# Dual_VCO_schematic_Thijn_en_Ralph.net
KiCad netlist of a schematic drawn in Altium Designer
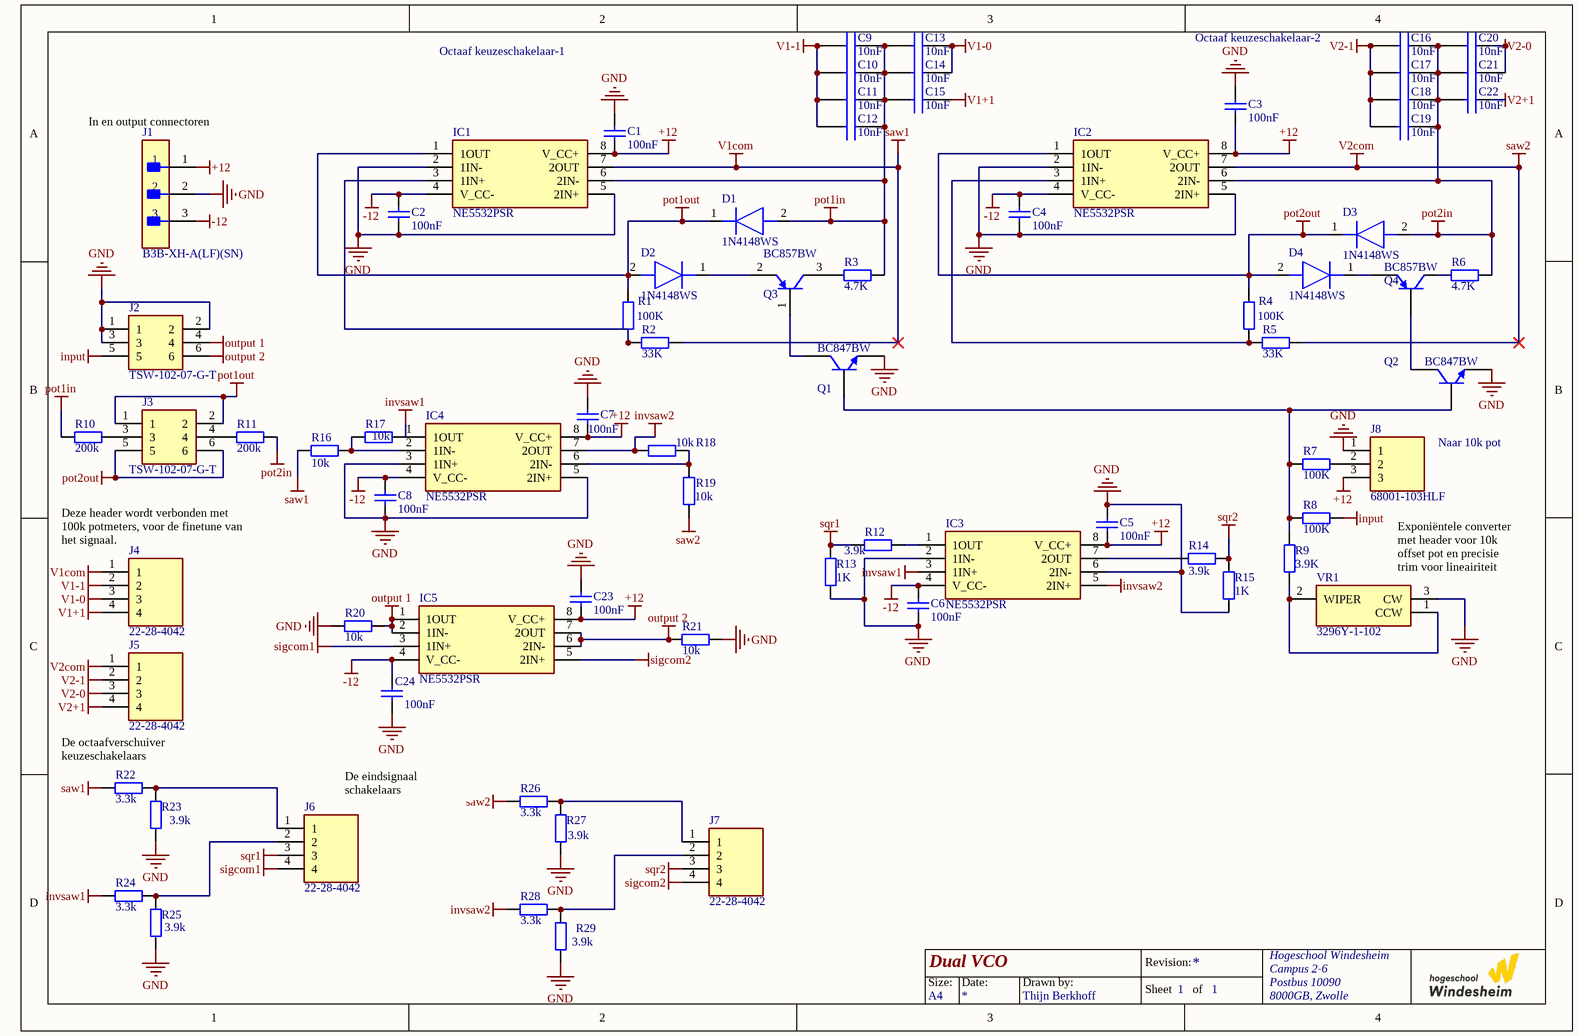
[diagram p0: Dual VCO schematic Thijn en Ralph.SchDoc]

(export (version "E")
  (design (tool "Eeschema 10.0.6"))
  (components
    (comp (ref "C1")
      (value "100nF")
      (footprint "C1206")
      (description "SMD Capacitor 1206")
      (fields (field (name "PUBLISHER") "Windesheim"))
      (libsource (lib "KookwekkerLibrary_v5_1") (part "Capacitor_1206"))
    )
    (comp (ref "C2")
      (value "100nF")
      (footprint "C1206")
      (description "SMD Capacitor 1206")
      (fields (field (name "PUBLISHER") "Windesheim"))
      (libsource (lib "KookwekkerLibrary_v5_1") (part "Capacitor_1206"))
    )
    (comp (ref "C3")
      (value "100nF")
      (footprint "C1206")
      (description "SMD Capacitor 1206")
      (fields (field (name "PUBLISHER") "Windesheim"))
      (libsource (lib "KookwekkerLibrary_v5_1") (part "Capacitor_1206"))
    )
    (comp (ref "C4")
      (value "100nF")
      (footprint "C1206")
      (description "SMD Capacitor 1206")
      (fields (field (name "PUBLISHER") "Windesheim"))
      (libsource (lib "KookwekkerLibrary_v5_1") (part "Capacitor_1206"))
    )
    (comp (ref "C5")
      (value "100nF")
      (footprint "C1206")
      (description "SMD Capacitor 1206")
      (fields (field (name "PUBLISHER") "Windesheim"))
      (libsource (lib "KookwekkerLibrary_v5_1") (part "Capacitor_1206"))
    )
    (comp (ref "C6")
      (value "100nF")
      (footprint "C1206")
      (description "SMD Capacitor 1206")
      (fields (field (name "PUBLISHER") "Windesheim"))
      (libsource (lib "KookwekkerLibrary_v5_1") (part "Capacitor_1206"))
    )
    (comp (ref "C7")
      (value "100nF")
      (footprint "C1206")
      (description "SMD Capacitor 1206")
      (fields (field (name "PUBLISHER") "Windesheim"))
      (libsource (lib "KookwekkerLibrary_v5_1") (part "Capacitor_1206"))
    )
    (comp (ref "C8")
      (value "100nF")
      (footprint "C1206")
      (description "SMD Capacitor 1206")
      (fields (field (name "PUBLISHER") "Windesheim"))
      (libsource (lib "KookwekkerLibrary_v5_1") (part "Capacitor_1206"))
    )
    (comp (ref "C9")
      (value "10nF")
      (footprint "SamacSys:R82MC2100DQ50J")
      (description "folie condensator")
      (fields
        (field (name "MANUFACTURER_PART_NUMBER") "R82MC2100DQ50J")
        (field (name "MOUSER PART NUMBER") "80-R82MC2100DQ50J")
      )
      (libsource (lib "*") (part "R82MC2100DQ50J"))
    )
    (comp (ref "C10")
      (value "10nF")
      (footprint "SamacSys:R82MC2100DQ50J")
      (description "folie condensator")
      (fields
        (field (name "MANUFACTURER_PART_NUMBER") "R82MC2100DQ50J")
        (field (name "MOUSER PART NUMBER") "80-R82MC2100DQ50J")
      )
      (libsource (lib "*") (part "R82MC2100DQ50J"))
    )
    (comp (ref "C11")
      (value "10nF")
      (footprint "SamacSys:R82MC2100DQ50J")
      (description "folie condensator")
      (fields
        (field (name "MANUFACTURER_PART_NUMBER") "R82MC2100DQ50J")
        (field (name "MOUSER PART NUMBER") "80-R82MC2100DQ50J")
      )
      (libsource (lib "*") (part "R82MC2100DQ50J"))
    )
    (comp (ref "C12")
      (value "10nF")
      (footprint "SamacSys:R82MC2100DQ50J")
      (description "folie condensator")
      (fields
        (field (name "MANUFACTURER_PART_NUMBER") "R82MC2100DQ50J")
        (field (name "MOUSER PART NUMBER") "80-R82MC2100DQ50J")
      )
      (libsource (lib "*") (part "R82MC2100DQ50J"))
    )
    (comp (ref "C13")
      (value "10nF")
      (footprint "SamacSys:R82MC2100DQ50J")
      (description "folie condensator")
      (fields
        (field (name "MANUFACTURER_PART_NUMBER") "R82MC2100DQ50J")
        (field (name "MOUSER PART NUMBER") "80-R82MC2100DQ50J")
      )
      (libsource (lib "*") (part "R82MC2100DQ50J"))
    )
    (comp (ref "C14")
      (value "10nF")
      (footprint "SamacSys:R82MC2100DQ50J")
      (description "folie condensator")
      (fields
        (field (name "MANUFACTURER_PART_NUMBER") "R82MC2100DQ50J")
        (field (name "MOUSER PART NUMBER") "80-R82MC2100DQ50J")
      )
      (libsource (lib "*") (part "R82MC2100DQ50J"))
    )
    (comp (ref "C15")
      (value "10nF")
      (footprint "SamacSys:R82MC2100DQ50J")
      (description "folie condensator")
      (fields
        (field (name "MANUFACTURER_PART_NUMBER") "R82MC2100DQ50J")
        (field (name "MOUSER PART NUMBER") "80-R82MC2100DQ50J")
      )
      (libsource (lib "*") (part "R82MC2100DQ50J"))
    )
    (comp (ref "C16")
      (value "10nF")
      (footprint "SamacSys:R82MC2100DQ50J")
      (description "folie condensator")
      (fields
        (field (name "MANUFACTURER_PART_NUMBER") "R82MC2100DQ50J")
        (field (name "MOUSER PART NUMBER") "80-R82MC2100DQ50J")
      )
      (libsource (lib "*") (part "R82MC2100DQ50J"))
    )
    (comp (ref "C17")
      (value "10nF")
      (footprint "SamacSys:R82MC2100DQ50J")
      (description "folie condensator")
      (fields
        (field (name "MANUFACTURER_PART_NUMBER") "R82MC2100DQ50J")
        (field (name "MOUSER PART NUMBER") "80-R82MC2100DQ50J")
      )
      (libsource (lib "*") (part "R82MC2100DQ50J"))
    )
    (comp (ref "C18")
      (value "10nF")
      (footprint "SamacSys:R82MC2100DQ50J")
      (description "folie condensator")
      (fields
        (field (name "MANUFACTURER_PART_NUMBER") "R82MC2100DQ50J")
        (field (name "MOUSER PART NUMBER") "80-R82MC2100DQ50J")
      )
      (libsource (lib "*") (part "R82MC2100DQ50J"))
    )
    (comp (ref "C19")
      (value "10nF")
      (footprint "SamacSys:R82MC2100DQ50J")
      (description "folie condensator")
      (fields
        (field (name "MANUFACTURER_PART_NUMBER") "R82MC2100DQ50J")
        (field (name "MOUSER PART NUMBER") "80-R82MC2100DQ50J")
      )
      (libsource (lib "*") (part "R82MC2100DQ50J"))
    )
    (comp (ref "C20")
      (value "10nF")
      (footprint "SamacSys:R82MC2100DQ50J")
      (description "folie condensator")
      (fields
        (field (name "MANUFACTURER_PART_NUMBER") "R82MC2100DQ50J")
        (field (name "MOUSER PART NUMBER") "80-R82MC2100DQ50J")
      )
      (libsource (lib "*") (part "R82MC2100DQ50J"))
    )
    (comp (ref "C21")
      (value "10nF")
      (footprint "SamacSys:R82MC2100DQ50J")
      (description "folie condensator")
      (fields
        (field (name "MANUFACTURER_PART_NUMBER") "R82MC2100DQ50J")
        (field (name "MOUSER PART NUMBER") "80-R82MC2100DQ50J")
      )
      (libsource (lib "*") (part "R82MC2100DQ50J"))
    )
    (comp (ref "C22")
      (value "10nF")
      (footprint "SamacSys:R82MC2100DQ50J")
      (description "folie condensator")
      (fields
        (field (name "MANUFACTURER_PART_NUMBER") "R82MC2100DQ50J")
        (field (name "MOUSER PART NUMBER") "80-R82MC2100DQ50J")
      )
      (libsource (lib "*") (part "R82MC2100DQ50J"))
    )
    (comp (ref "C23")
      (value "100nF")
      (footprint "C1206")
      (description "SMD Capacitor 1206")
      (fields (field (name "PUBLISHER") "Windesheim"))
      (libsource (lib "KookwekkerLibrary_v5_1") (part "Capacitor_1206"))
    )
    (comp (ref "C24")
      (value "100nF")
      (footprint "C1206")
      (description "SMD Capacitor 1206")
      (fields (field (name "PUBLISHER") "Windesheim"))
      (libsource (lib "KookwekkerLibrary_v5_1") (part "Capacitor_1206"))
    )
    (comp (ref "D1")
      (value "1N4148WS")
      (footprint "SamacSys:SODFL2512X90N")
      (description "Diode")
      (fields (field (name "MOUSER PART NUMBER") "512-1N4148WS"))
      (libsource (lib "*") (part "1N4148WS"))
    )
    (comp (ref "D2")
      (value "1N4148WS")
      (footprint "SamacSys:SODFL2512X90N")
      (description "Diode")
      (fields (field (name "MOUSER PART NUMBER") "512-1N4148WS"))
      (libsource (lib "*") (part "1N4148WS"))
    )
    (comp (ref "D3")
      (value "1N4148WS")
      (footprint "SamacSys:SODFL2512X90N")
      (description "Diode")
      (fields (field (name "MOUSER PART NUMBER") "512-1N4148WS"))
      (libsource (lib "*") (part "1N4148WS"))
    )
    (comp (ref "D4")
      (value "1N4148WS")
      (footprint "SamacSys:SODFL2512X90N")
      (description "Diode")
      (fields (field (name "MOUSER PART NUMBER") "512-1N4148WS"))
      (libsource (lib "*") (part "1N4148WS"))
    )
    (comp (ref "IC1")
      (value "NE5532PSR")
      (footprint "SamacSys:SOIC127P780X200-8N")
      (description "Integrated Circuit")
      (fields (field (name "MOUSER PART NUMBER") "595-NE5532PSR"))
      (libsource (lib "*") (part "NE5532PSR"))
    )
    (comp (ref "IC2")
      (value "NE5532PSR")
      (footprint "SamacSys:SOIC127P780X200-8N")
      (description "Integrated Circuit")
      (fields (field (name "MOUSER PART NUMBER") "595-NE5532PSR"))
      (libsource (lib "*") (part "NE5532PSR"))
    )
    (comp (ref "IC3")
      (value "NE5532PSR")
      (footprint "SamacSys:SOIC127P780X200-8N")
      (description "Integrated Circuit")
      (fields (field (name "MOUSER PART NUMBER") "595-NE5532PSR"))
      (libsource (lib "*") (part "NE5532PSR"))
    )
    (comp (ref "IC4")
      (value "NE5532PSR")
      (footprint "SamacSys:SOIC127P780X200-8N")
      (description "Integrated Circuit")
      (fields (field (name "MOUSER PART NUMBER") "595-NE5532PSR"))
      (libsource (lib "*") (part "NE5532PSR"))
    )
    (comp (ref "IC5")
      (value "NE5532PSR")
      (footprint "SamacSys:SOIC127P780X200-8N")
      (description "Integrated Circuit")
      (fields (field (name "MOUSER PART NUMBER") "595-NE5532PSR"))
      (libsource (lib "*") (part "NE5532PSR"))
    )
    (comp (ref "J1")
      (value "B3B-XH-A(LF)(SN)")
      (footprint "FP-B3B-XH-A_LF_SN-MFG")
      (description "CONN HEADER VERT 3POS 2.5MM")
      (libsource (lib "Altium Content Vault") (part "0d3f023dd272f625e17a2be33dea85f"))
    )
    (comp (ref "J2")
      (value "TSW-102-07-G-T")
      (footprint "SamacSys:HDRV6W64P254_3X2_508X762X838P")
      (description "Connector")
      (fields (field (name "MOUSER PART NUMBER") "200-TSW10207GT"))
      (libsource (lib "*") (part "TSW-102-07-G-T"))
    )
    (comp (ref "J3")
      (value "TSW-102-07-G-T")
      (footprint "SamacSys:HDRV6W64P254_3X2_508X762X838P")
      (description "Connector")
      (fields (field (name "MOUSER PART NUMBER") "200-TSW10207GT"))
      (libsource (lib "*") (part "TSW-102-07-G-T"))
    )
    (comp (ref "J4")
      (value "22-28-4042")
      (footprint "SamacSys:HDRV4W66P0X254_1X4_1016X249X1003P")
      (description "Connector")
      (fields (field (name "MOUSER PART NUMBER") "538-22-28-4042"))
      (libsource (lib "*") (part "22-28-4042"))
    )
    (comp (ref "J5")
      (value "22-28-4042")
      (footprint "SamacSys:HDRV4W66P0X254_1X4_1016X249X1003P")
      (description "Connector")
      (fields (field (name "MOUSER PART NUMBER") "538-22-28-4042"))
      (libsource (lib "*") (part "22-28-4042"))
    )
    (comp (ref "J6")
      (value "22-28-4042")
      (footprint "SamacSys:HDRV4W66P0X254_1X4_1016X249X1003P")
      (description "Connector")
      (fields (field (name "MOUSER PART NUMBER") "538-22-28-4042"))
      (libsource (lib "*") (part "22-28-4042"))
    )
    (comp (ref "J7")
      (value "22-28-4042")
      (footprint "SamacSys:HDRV4W66P0X254_1X4_1016X249X1003P")
      (description "Connector")
      (fields (field (name "MOUSER PART NUMBER") "538-22-28-4042"))
      (libsource (lib "*") (part "22-28-4042"))
    )
    (comp (ref "J8")
      (value "68001-103HLF")
      (footprint "SamacSys:68001103HLF")
      (description "Connector")
      (libsource (lib "*") (part "68001-103HLF"))
    )
    (comp (ref "Q1")
      (value "BC847BW")
      (footprint "SOT23")
      (libsource (lib "KookwekkerLibrary_v5_1") (part "BC847BW"))
    )
    (comp (ref "Q2")
      (value "BC847BW")
      (footprint "SOT23")
      (libsource (lib "KookwekkerLibrary_v5_1") (part "BC847BW"))
    )
    (comp (ref "Q3")
      (value "BC857BW")
      (footprint "SOT23")
      (libsource (lib "KookwekkerLibrary_v5_1") (part "BC857BW"))
    )
    (comp (ref "Q4") (value "BC857BW") (footprint "SOT23") (libsource (lib "") (part "BC857BW_1")))
    (comp (ref "R1")
      (value "100K")
      (footprint "R1206")
      (description "SMD Resistor 1206")
      (fields (field (name "PUBLISHER") "Windesheim"))
      (libsource (lib "") (part "Resistor_1206_2"))
    )
    (comp (ref "R2")
      (value "33K")
      (footprint "R1206")
      (description "SMD Resistor 1206")
      (fields (field (name "PUBLISHER") "Windesheim"))
      (libsource (lib "KookwekkerLibrary_v5_1") (part "Resistor_1206"))
    )
    (comp (ref "R3")
      (value "4.7K")
      (footprint "R1206")
      (description "SMD Resistor 1206")
      (fields (field (name "PUBLISHER") "Windesheim"))
      (libsource (lib "KookwekkerLibrary_v5_1") (part "Resistor_1206"))
    )
    (comp (ref "R4")
      (value "100K")
      (footprint "R1206")
      (description "SMD Resistor 1206")
      (fields (field (name "PUBLISHER") "Windesheim"))
      (libsource (lib "") (part "Resistor_1206_2"))
    )
    (comp (ref "R5")
      (value "33K")
      (footprint "R1206")
      (description "SMD Resistor 1206")
      (fields (field (name "PUBLISHER") "Windesheim"))
      (libsource (lib "KookwekkerLibrary_v5_1") (part "Resistor_1206"))
    )
    (comp (ref "R6")
      (value "4.7K")
      (footprint "R1206")
      (description "SMD Resistor 1206")
      (fields (field (name "PUBLISHER") "Windesheim"))
      (libsource (lib "KookwekkerLibrary_v5_1") (part "Resistor_1206"))
    )
    (comp (ref "R7")
      (value "100K")
      (footprint "R1206")
      (description "SMD Resistor 1206")
      (fields (field (name "PUBLISHER") "Windesheim"))
      (libsource (lib "") (part "Resistor_1206_1"))
    )
    (comp (ref "R8")
      (value "100K")
      (footprint "R1206")
      (description "SMD Resistor 1206")
      (fields (field (name "PUBLISHER") "Windesheim"))
      (libsource (lib "KookwekkerLibrary_v5_1") (part "Resistor_1206"))
    )
    (comp (ref "R9")
      (value "3.9K")
      (footprint "R1206")
      (description "SMD Resistor 1206")
      (fields (field (name "PUBLISHER") "Windesheim"))
      (libsource (lib "") (part "Resistor_1206_2"))
    )
    (comp (ref "R10")
      (value "200k")
      (footprint "R1206")
      (description "SMD Resistor 1206")
      (fields (field (name "PUBLISHER") "Windesheim"))
      (libsource (lib "KookwekkerLibrary_v5_1") (part "Resistor_1206"))
    )
    (comp (ref "R11")
      (value "200k")
      (footprint "R1206")
      (description "SMD Resistor 1206")
      (fields (field (name "PUBLISHER") "Windesheim"))
      (libsource (lib "") (part "Resistor_1206_2"))
    )
    (comp (ref "R12")
      (value "3.9k")
      (footprint "R1206")
      (description "SMD Resistor 1206")
      (fields (field (name "PUBLISHER") "Windesheim"))
      (libsource (lib "KookwekkerLibrary_v5_1") (part "Resistor_1206"))
    )
    (comp (ref "R13")
      (value "1K")
      (footprint "R1206")
      (description "SMD Resistor 1206")
      (fields (field (name "PUBLISHER") "Windesheim"))
      (libsource (lib "") (part "Resistor_1206_2"))
    )
    (comp (ref "R14")
      (value "3.9k")
      (footprint "R1206")
      (description "SMD Resistor 1206")
      (fields (field (name "PUBLISHER") "Windesheim"))
      (libsource (lib "KookwekkerLibrary_v5_1") (part "Resistor_1206"))
    )
    (comp (ref "R15")
      (value "1K")
      (footprint "R1206")
      (description "SMD Resistor 1206")
      (fields (field (name "PUBLISHER") "Windesheim"))
      (libsource (lib "") (part "Resistor_1206_2"))
    )
    (comp (ref "R16")
      (value "10k")
      (footprint "R1206")
      (description "SMD Resistor 1206")
      (fields (field (name "PUBLISHER") "Windesheim"))
      (libsource (lib "KookwekkerLibrary_v5_1") (part "Resistor_1206"))
    )
    (comp (ref "R17")
      (value "10k")
      (footprint "R1206")
      (description "SMD Resistor 1206")
      (fields (field (name "PUBLISHER") "Windesheim"))
      (libsource (lib "") (part "Resistor_1206_1"))
    )
    (comp (ref "R18")
      (value "10k")
      (footprint "R1206")
      (description "SMD Resistor 1206")
      (fields (field (name "PUBLISHER") "Windesheim"))
      (libsource (lib "KookwekkerLibrary_v5_1") (part "Resistor_1206"))
    )
    (comp (ref "R19")
      (value "10k")
      (footprint "R1206")
      (description "SMD Resistor 1206")
      (fields (field (name "PUBLISHER") "Windesheim"))
      (libsource (lib "") (part "Resistor_1206_3"))
    )
    (comp (ref "R20")
      (value "10k")
      (footprint "R1206")
      (description "SMD Resistor 1206")
      (fields (field (name "PUBLISHER") "Windesheim"))
      (libsource (lib "") (part "Resistor_1206_1"))
    )
    (comp (ref "R21")
      (value "10k")
      (footprint "R1206")
      (description "SMD Resistor 1206")
      (fields (field (name "PUBLISHER") "Windesheim"))
      (libsource (lib "KookwekkerLibrary_v5_1") (part "Resistor_1206"))
    )
    (comp (ref "R22")
      (value "3.3k")
      (footprint "R1206")
      (description "SMD Resistor 1206")
      (fields (field (name "PUBLISHER") "Windesheim"))
      (libsource (lib "KookwekkerLibrary_v5_1") (part "Resistor_1206"))
    )
    (comp (ref "R23")
      (value "3.9k")
      (footprint "R1206")
      (description "SMD Resistor 1206")
      (fields (field (name "PUBLISHER") "Windesheim"))
      (libsource (lib "") (part "Resistor_1206_2"))
    )
    (comp (ref "R24")
      (value "3.3k")
      (footprint "R1206")
      (description "SMD Resistor 1206")
      (fields (field (name "PUBLISHER") "Windesheim"))
      (libsource (lib "KookwekkerLibrary_v5_1") (part "Resistor_1206"))
    )
    (comp (ref "R25")
      (value "3.9k")
      (footprint "R1206")
      (description "SMD Resistor 1206")
      (fields (field (name "PUBLISHER") "Windesheim"))
      (libsource (lib "") (part "Resistor_1206_2"))
    )
    (comp (ref "R26")
      (value "3.3k")
      (footprint "R1206")
      (description "SMD Resistor 1206")
      (fields (field (name "PUBLISHER") "Windesheim"))
      (libsource (lib "KookwekkerLibrary_v5_1") (part "Resistor_1206"))
    )
    (comp (ref "R27")
      (value "3.9k")
      (footprint "R1206")
      (description "SMD Resistor 1206")
      (fields (field (name "PUBLISHER") "Windesheim"))
      (libsource (lib "") (part "Resistor_1206_2"))
    )
    (comp (ref "R28")
      (value "3.3k")
      (footprint "R1206")
      (description "SMD Resistor 1206")
      (fields (field (name "PUBLISHER") "Windesheim"))
      (libsource (lib "KookwekkerLibrary_v5_1") (part "Resistor_1206"))
    )
    (comp (ref "R29")
      (value "3.9k")
      (footprint "R1206")
      (description "SMD Resistor 1206")
      (fields (field (name "PUBLISHER") "Windesheim"))
      (libsource (lib "") (part "Resistor_1206_2"))
    )
    (comp (ref "VR1")
      (value "3296Y-1-102")
      (footprint "SamacSys:3296Y1102")
      (description "Variable Resistor")
      (fields (field (name "MOUSER PART NUMBER") "652-3296Y-1-102"))
      (libsource (lib "*") (part "3296Y-1-102"))
    )
  )
  (nets
    (net (code "1") (name "+12") (class "Default")
      (node (ref "C1") (pin "1") (pinfunction "1_1") (pintype "passive"))
      (node (ref "C23") (pin "1") (pinfunction "1_1") (pintype "passive"))
      (node (ref "C3") (pin "1") (pinfunction "1_1") (pintype "passive"))
      (node (ref "C5") (pin "1") (pinfunction "1_1") (pintype "passive"))
      (node (ref "C7") (pin "1") (pinfunction "1_1") (pintype "passive"))
      (node (ref "IC1") (pin "8") (pinfunction "V_CC+_8") (pintype "passive"))
      (node (ref "IC2") (pin "8") (pinfunction "V_CC+_8") (pintype "passive"))
      (node (ref "IC3") (pin "8") (pinfunction "V_CC+_8") (pintype "passive"))
      (node (ref "IC4") (pin "8") (pinfunction "V_CC+_8") (pintype "passive"))
      (node (ref "IC5") (pin "8") (pinfunction "V_CC+_8") (pintype "passive"))
      (node (ref "J1") (pin "1") (pinfunction "1_1") (pintype "passive"))
      (node (ref "J8") (pin "3") (pinfunction "3_3") (pintype "passive"))
    )
    (net (code "2") (name "-12") (class "Default")
      (node (ref "C2") (pin "2") (pinfunction "2_2") (pintype "passive"))
      (node (ref "C24") (pin "2") (pinfunction "2_2") (pintype "passive"))
      (node (ref "C4") (pin "2") (pinfunction "2_2") (pintype "passive"))
      (node (ref "C6") (pin "2") (pinfunction "2_2") (pintype "passive"))
      (node (ref "C8") (pin "2") (pinfunction "2_2") (pintype "passive"))
      (node (ref "IC1") (pin "4") (pinfunction "V_CC-_4") (pintype "passive"))
      (node (ref "IC2") (pin "4") (pinfunction "V_CC-_4") (pintype "passive"))
      (node (ref "IC3") (pin "4") (pinfunction "V_CC-_4") (pintype "passive"))
      (node (ref "IC4") (pin "4") (pinfunction "V_CC-_4") (pintype "passive"))
      (node (ref "IC5") (pin "4") (pinfunction "V_CC-_4") (pintype "passive"))
      (node (ref "J1") (pin "3") (pinfunction "3_3") (pintype "passive"))
    )
    (net (code "3") (name "GND") (class "Default")
      (node (ref "C1") (pin "2") (pinfunction "2_2") (pintype "passive"))
      (node (ref "C2") (pin "1") (pinfunction "1_1") (pintype "passive"))
      (node (ref "C23") (pin "2") (pinfunction "2_2") (pintype "passive"))
      (node (ref "C24") (pin "1") (pinfunction "1_1") (pintype "passive"))
      (node (ref "C3") (pin "2") (pinfunction "2_2") (pintype "passive"))
      (node (ref "C4") (pin "1") (pinfunction "1_1") (pintype "passive"))
      (node (ref "C5") (pin "2") (pinfunction "2_2") (pintype "passive"))
      (node (ref "C6") (pin "1") (pinfunction "1_1") (pintype "passive"))
      (node (ref "C7") (pin "2") (pinfunction "2_2") (pintype "passive"))
      (node (ref "C8") (pin "1") (pinfunction "1_1") (pintype "passive"))
      (node (ref "IC1") (pin "2") (pinfunction "1IN-_2") (pintype "passive"))
      (node (ref "IC1") (pin "5") (pinfunction "2IN+_5") (pintype "passive"))
      (node (ref "IC2") (pin "2") (pinfunction "1IN-_2") (pintype "passive"))
      (node (ref "IC2") (pin "5") (pinfunction "2IN+_5") (pintype "passive"))
      (node (ref "IC3") (pin "2") (pinfunction "1IN-_2") (pintype "passive"))
      (node (ref "IC3") (pin "6") (pinfunction "2IN-_6") (pintype "passive"))
      (node (ref "IC4") (pin "3") (pinfunction "1IN+_3") (pintype "passive"))
      (node (ref "IC4") (pin "5") (pinfunction "2IN+_5") (pintype "passive"))
      (node (ref "J1") (pin "2") (pinfunction "2_2") (pintype "passive"))
      (node (ref "J2") (pin "1") (pinfunction "1_1") (pintype "passive"))
      (node (ref "J2") (pin "2") (pinfunction "2_2") (pintype "passive"))
      (node (ref "J2") (pin "3") (pinfunction "3_3") (pintype "passive"))
      (node (ref "J8") (pin "1") (pinfunction "1_1") (pintype "passive"))
      (node (ref "Q1") (pin "2") (pinfunction "E_2") (pintype "passive"))
      (node (ref "Q2") (pin "2") (pinfunction "E_2") (pintype "passive"))
      (node (ref "R13") (pin "1") (pinfunction "1_1") (pintype "passive"))
      (node (ref "R15") (pin "1") (pinfunction "1_1") (pintype "passive"))
      (node (ref "R20") (pin "2") (pinfunction "2_2") (pintype "passive"))
      (node (ref "R21") (pin "2") (pinfunction "2_2") (pintype "passive"))
      (node (ref "R23") (pin "1") (pinfunction "1_1") (pintype "passive"))
      (node (ref "R25") (pin "1") (pinfunction "1_1") (pintype "passive"))
      (node (ref "R27") (pin "1") (pinfunction "1_1") (pintype "passive"))
      (node (ref "R29") (pin "1") (pinfunction "1_1") (pintype "passive"))
      (node (ref "VR1") (pin "3") (pinfunction "CW_3") (pintype "passive"))
    )
    (net (code "4") (name "Net-(D2-K)") (class "Default")
      (node (ref "D2") (pin "1") (pinfunction "K_1") (pintype "passive"))
      (node (ref "Q3") (pin "2") (pinfunction "E_2") (pintype "passive"))
    )
    (net (code "5") (name "Net-(D4-K)") (class "Default")
      (node (ref "D4") (pin "1") (pinfunction "K_1") (pintype "passive"))
      (node (ref "Q4") (pin "2") (pinfunction "E_2") (pintype "passive"))
    )
    (net (code "6") (name "Net-(IC1-1IN+)") (class "Default")
      (node (ref "IC1") (pin "3") (pinfunction "1IN+_3") (pintype "passive"))
      (node (ref "R1") (pin "1") (pinfunction "1_1") (pintype "passive"))
      (node (ref "R2") (pin "1") (pinfunction "1_1") (pintype "passive"))
    )
    (net (code "7") (name "Net-(IC2-1IN+)") (class "Default")
      (node (ref "IC2") (pin "3") (pinfunction "1IN+_3") (pintype "passive"))
      (node (ref "R4") (pin "1") (pinfunction "1_1") (pintype "passive"))
      (node (ref "R5") (pin "1") (pinfunction "1_1") (pintype "passive"))
    )
    (net (code "8") (name "Net-(IC3-1OUT)") (class "Default")
      (node (ref "IC3") (pin "1") (pinfunction "1OUT_1") (pintype "passive"))
      (node (ref "R12") (pin "2") (pinfunction "2_2") (pintype "passive"))
    )
    (net (code "9") (name "Net-(IC3-2OUT)") (class "Default")
      (node (ref "IC3") (pin "7") (pinfunction "2OUT_7") (pintype "passive"))
      (node (ref "R14") (pin "1") (pinfunction "1_1") (pintype "passive"))
    )
    (net (code "10") (name "Net-(IC4-1IN-)") (class "Default")
      (node (ref "IC4") (pin "2") (pinfunction "1IN-_2") (pintype "passive"))
      (node (ref "R16") (pin "2") (pinfunction "2_2") (pintype "passive"))
      (node (ref "R17") (pin "2") (pinfunction "2_2") (pintype "passive"))
    )
    (net (code "11") (name "Net-(IC4-2IN-)") (class "Default")
      (node (ref "IC4") (pin "6") (pinfunction "2IN-_6") (pintype "passive"))
      (node (ref "R18") (pin "2") (pinfunction "2_2") (pintype "passive"))
      (node (ref "R19") (pin "1") (pinfunction "1_1") (pintype "passive"))
    )
    (net (code "12") (name "Net-(J3-Pad3)") (class "Default")
      (node (ref "J3") (pin "3") (pinfunction "3_3") (pintype "passive"))
      (node (ref "R10") (pin "2") (pinfunction "2_2") (pintype "passive"))
    )
    (net (code "13") (name "Net-(J3-Pad4)") (class "Default")
      (node (ref "J3") (pin "4") (pinfunction "4_4") (pintype "passive"))
      (node (ref "R11") (pin "1") (pinfunction "1_1") (pintype "passive"))
    )
    (net (code "14") (name "Net-(J6-Pad1)") (class "Default")
      (node (ref "J6") (pin "1") (pinfunction "1_1") (pintype "passive"))
      (node (ref "R22") (pin "2") (pinfunction "2_2") (pintype "passive"))
      (node (ref "R23") (pin "2") (pinfunction "2_2") (pintype "passive"))
    )
    (net (code "15") (name "Net-(J6-Pad2)") (class "Default")
      (node (ref "J6") (pin "2") (pinfunction "2_2") (pintype "passive"))
      (node (ref "R24") (pin "2") (pinfunction "2_2") (pintype "passive"))
      (node (ref "R25") (pin "2") (pinfunction "2_2") (pintype "passive"))
    )
    (net (code "16") (name "Net-(J7-Pad1)") (class "Default")
      (node (ref "J7") (pin "1") (pinfunction "1_1") (pintype "passive"))
      (node (ref "R26") (pin "2") (pinfunction "2_2") (pintype "passive"))
      (node (ref "R27") (pin "2") (pinfunction "2_2") (pintype "passive"))
    )
    (net (code "17") (name "Net-(J7-Pad2)") (class "Default")
      (node (ref "J7") (pin "2") (pinfunction "2_2") (pintype "passive"))
      (node (ref "R28") (pin "2") (pinfunction "2_2") (pintype "passive"))
      (node (ref "R29") (pin "2") (pinfunction "2_2") (pintype "passive"))
    )
    (net (code "18") (name "Net-(J8-Pad2)") (class "Default")
      (node (ref "J8") (pin "2") (pinfunction "2_2") (pintype "passive"))
      (node (ref "R7") (pin "1") (pinfunction "1_1") (pintype "passive"))
    )
    (net (code "19") (name "Net-(Q1-B)") (class "Default")
      (node (ref "Q1") (pin "1") (pinfunction "B_1") (pintype "passive"))
      (node (ref "Q2") (pin "1") (pinfunction "B_1") (pintype "passive"))
      (node (ref "R7") (pin "2") (pinfunction "2_2") (pintype "passive"))
      (node (ref "R8") (pin "1") (pinfunction "1_1") (pintype "passive"))
      (node (ref "R9") (pin "2") (pinfunction "2_2") (pintype "passive"))
    )
    (net (code "20") (name "Net-(Q1-C)") (class "Default")
      (node (ref "Q1") (pin "3") (pinfunction "C_3") (pintype "passive"))
      (node (ref "Q3") (pin "1") (pinfunction "B_1") (pintype "passive"))
    )
    (net (code "21") (name "Net-(Q2-C)") (class "Default")
      (node (ref "Q2") (pin "3") (pinfunction "C_3") (pintype "passive"))
      (node (ref "Q4") (pin "1") (pinfunction "B_1") (pintype "passive"))
    )
    (net (code "22") (name "Net-(Q3-C)") (class "Default")
      (node (ref "Q3") (pin "3") (pinfunction "C_3") (pintype "passive"))
      (node (ref "R3") (pin "1") (pinfunction "1_1") (pintype "passive"))
    )
    (net (code "23") (name "Net-(Q4-C)") (class "Default")
      (node (ref "Q4") (pin "3") (pinfunction "C_3") (pintype "passive"))
      (node (ref "R6") (pin "1") (pinfunction "1_1") (pintype "passive"))
    )
    (net (code "24") (name "Net-(VR1-CCW)") (class "Default")
      (node (ref "R9") (pin "1") (pinfunction "1_1") (pintype "passive"))
      (node (ref "VR1") (pin "1") (pinfunction "CCW_1") (pintype "passive"))
      (node (ref "VR1") (pin "2") (pinfunction "WIPER_2") (pintype "passive"))
    )
    (net (code "25") (name "V1+1") (class "Default")
      (node (ref "C15") (pin "1") (pinfunction "1_1") (pintype "passive"))
      (node (ref "J4") (pin "4") (pinfunction "4_4") (pintype "passive"))
    )
    (net (code "26") (name "V1-0") (class "Default")
      (node (ref "C13") (pin "1") (pinfunction "1_1") (pintype "passive"))
      (node (ref "C14") (pin "1") (pinfunction "1_1") (pintype "passive"))
      (node (ref "J4") (pin "3") (pinfunction "3_3") (pintype "passive"))
    )
    (net (code "27") (name "V1-1") (class "Default")
      (node (ref "C10") (pin "1") (pinfunction "1_1") (pintype "passive"))
      (node (ref "C11") (pin "1") (pinfunction "1_1") (pintype "passive"))
      (node (ref "C12") (pin "1") (pinfunction "1_1") (pintype "passive"))
      (node (ref "C9") (pin "1") (pinfunction "1_1") (pintype "passive"))
      (node (ref "J4") (pin "2") (pinfunction "2_2") (pintype "passive"))
    )
    (net (code "28") (name "V1com") (class "Default")
      (node (ref "IC1") (pin "7") (pinfunction "2OUT_7") (pintype "passive"))
      (node (ref "J4") (pin "1") (pinfunction "1_1") (pintype "passive"))
      (node (ref "R16") (pin "1") (pinfunction "1_1") (pintype "passive"))
      (node (ref "R2") (pin "2") (pinfunction "2_2") (pintype "passive"))
      (node (ref "R22") (pin "1") (pinfunction "1_1") (pintype "passive"))
    )
    (net (code "29") (name "V2+1") (class "Default")
      (node (ref "C22") (pin "2") (pinfunction "2_2") (pintype "passive"))
      (node (ref "J5") (pin "4") (pinfunction "4_4") (pintype "passive"))
    )
    (net (code "30") (name "V2-0") (class "Default")
      (node (ref "C20") (pin "2") (pinfunction "2_2") (pintype "passive"))
      (node (ref "C21") (pin "2") (pinfunction "2_2") (pintype "passive"))
      (node (ref "J5") (pin "3") (pinfunction "3_3") (pintype "passive"))
    )
    (net (code "31") (name "V2-1") (class "Default")
      (node (ref "C16") (pin "1") (pinfunction "1_1") (pintype "passive"))
      (node (ref "C17") (pin "1") (pinfunction "1_1") (pintype "passive"))
      (node (ref "C18") (pin "1") (pinfunction "1_1") (pintype "passive"))
      (node (ref "C19") (pin "1") (pinfunction "1_1") (pintype "passive"))
      (node (ref "J5") (pin "2") (pinfunction "2_2") (pintype "passive"))
    )
    (net (code "32") (name "V2com") (class "Default")
      (node (ref "IC2") (pin "7") (pinfunction "2OUT_7") (pintype "passive"))
      (node (ref "J5") (pin "1") (pinfunction "1_1") (pintype "passive"))
      (node (ref "R19") (pin "2") (pinfunction "2_2") (pintype "passive"))
      (node (ref "R26") (pin "1") (pinfunction "1_1") (pintype "passive"))
      (node (ref "R5") (pin "2") (pinfunction "2_2") (pintype "passive"))
    )
    (net (code "33") (name "input") (class "Default")
      (node (ref "J2") (pin "5") (pinfunction "5_5") (pintype "passive"))
      (node (ref "R8") (pin "2") (pinfunction "2_2") (pintype "passive"))
    )
    (net (code "34") (name "invsaw1") (class "Default")
      (node (ref "IC3") (pin "3") (pinfunction "1IN+_3") (pintype "passive"))
      (node (ref "R17") (pin "1") (pinfunction "1_1") (pintype "passive"))
      (node (ref "R24") (pin "1") (pinfunction "1_1") (pintype "passive"))
    )
    (net (code "35") (name "invsaw2") (class "Default")
      (node (ref "IC3") (pin "5") (pinfunction "2IN+_5") (pintype "passive"))
      (node (ref "IC4") (pin "7") (pinfunction "2OUT_7") (pintype "passive"))
      (node (ref "R18") (pin "1") (pinfunction "1_1") (pintype "passive"))
      (node (ref "R28") (pin "1") (pinfunction "1_1") (pintype "passive"))
    )
    (net (code "36") (name "output 1") (class "Default")
      (node (ref "IC5") (pin "1") (pinfunction "1OUT_1") (pintype "passive"))
      (node (ref "IC5") (pin "2") (pinfunction "1IN-_2") (pintype "passive"))
      (node (ref "J2") (pin "4") (pinfunction "4_4") (pintype "passive"))
      (node (ref "R20") (pin "1") (pinfunction "1_1") (pintype "passive"))
    )
    (net (code "37") (name "output 2") (class "Default")
      (node (ref "IC5") (pin "6") (pinfunction "2IN-_6") (pintype "passive"))
      (node (ref "IC5") (pin "7") (pinfunction "2OUT_7") (pintype "passive"))
      (node (ref "J2") (pin "6") (pinfunction "6_6") (pintype "passive"))
      (node (ref "R21") (pin "1") (pinfunction "1_1") (pintype "passive"))
    )
    (net (code "38") (name "pot1in") (class "Default")
      (node (ref "C10") (pin "2") (pinfunction "2_2") (pintype "passive"))
      (node (ref "C11") (pin "2") (pinfunction "2_2") (pintype "passive"))
      (node (ref "C12") (pin "2") (pinfunction "2_2") (pintype "passive"))
      (node (ref "C13") (pin "2") (pinfunction "2_2") (pintype "passive"))
      (node (ref "C14") (pin "2") (pinfunction "2_2") (pintype "passive"))
      (node (ref "C15") (pin "2") (pinfunction "2_2") (pintype "passive"))
      (node (ref "C9") (pin "2") (pinfunction "2_2") (pintype "passive"))
      (node (ref "D1") (pin "2") (pinfunction "A_2") (pintype "passive"))
      (node (ref "IC1") (pin "6") (pinfunction "2IN-_6") (pintype "passive"))
      (node (ref "R10") (pin "1") (pinfunction "1_1") (pintype "passive"))
      (node (ref "R3") (pin "2") (pinfunction "2_2") (pintype "passive"))
    )
    (net (code "39") (name "pot1out") (class "Default")
      (node (ref "D1") (pin "1") (pinfunction "K_1") (pintype "passive"))
      (node (ref "D2") (pin "2") (pinfunction "A_2") (pintype "passive"))
      (node (ref "IC1") (pin "1") (pinfunction "1OUT_1") (pintype "passive"))
      (node (ref "J3") (pin "1") (pinfunction "1_1") (pintype "passive"))
      (node (ref "J3") (pin "2") (pinfunction "2_2") (pintype "passive"))
      (node (ref "R1") (pin "2") (pinfunction "2_2") (pintype "passive"))
    )
    (net (code "40") (name "pot2in") (class "Default")
      (node (ref "C16") (pin "2") (pinfunction "2_2") (pintype "passive"))
      (node (ref "C17") (pin "2") (pinfunction "2_2") (pintype "passive"))
      (node (ref "C18") (pin "2") (pinfunction "2_2") (pintype "passive"))
      (node (ref "C19") (pin "2") (pinfunction "2_2") (pintype "passive"))
      (node (ref "C20") (pin "1") (pinfunction "1_1") (pintype "passive"))
      (node (ref "C21") (pin "1") (pinfunction "1_1") (pintype "passive"))
      (node (ref "C22") (pin "1") (pinfunction "1_1") (pintype "passive"))
      (node (ref "D3") (pin "2") (pinfunction "A_2") (pintype "passive"))
      (node (ref "IC2") (pin "6") (pinfunction "2IN-_6") (pintype "passive"))
      (node (ref "R11") (pin "2") (pinfunction "2_2") (pintype "passive"))
      (node (ref "R6") (pin "2") (pinfunction "2_2") (pintype "passive"))
    )
    (net (code "41") (name "pot2out") (class "Default")
      (node (ref "D3") (pin "1") (pinfunction "K_1") (pintype "passive"))
      (node (ref "D4") (pin "2") (pinfunction "A_2") (pintype "passive"))
      (node (ref "IC2") (pin "1") (pinfunction "1OUT_1") (pintype "passive"))
      (node (ref "J3") (pin "5") (pinfunction "5_5") (pintype "passive"))
      (node (ref "J3") (pin "6") (pinfunction "6_6") (pintype "passive"))
      (node (ref "R4") (pin "2") (pinfunction "2_2") (pintype "passive"))
    )
    (net (code "42") (name "sigcom1") (class "Default")
      (node (ref "IC5") (pin "3") (pinfunction "1IN+_3") (pintype "passive"))
      (node (ref "J6") (pin "4") (pinfunction "4_4") (pintype "passive"))
    )
    (net (code "43") (name "sigcom2") (class "Default")
      (node (ref "IC5") (pin "5") (pinfunction "2IN+_5") (pintype "passive"))
      (node (ref "J7") (pin "4") (pinfunction "4_4") (pintype "passive"))
    )
    (net (code "44") (name "sqr1") (class "Default")
      (node (ref "J6") (pin "3") (pinfunction "3_3") (pintype "passive"))
      (node (ref "R12") (pin "1") (pinfunction "1_1") (pintype "passive"))
      (node (ref "R13") (pin "2") (pinfunction "2_2") (pintype "passive"))
    )
    (net (code "45") (name "sqr2") (class "Default")
      (node (ref "J7") (pin "3") (pinfunction "3_3") (pintype "passive"))
      (node (ref "R14") (pin "2") (pinfunction "2_2") (pintype "passive"))
      (node (ref "R15") (pin "2") (pinfunction "2_2") (pintype "passive"))
    )
    (net (code "46") (name "unconnected-(IC4-1OUT-Pad1)") (class "Default")
      (node (ref "IC4") (pin "1") (pinfunction "1OUT_1") (pintype "passive"))
    )
  )
)
